# LED_Readout_Resistors.net
KiCad netlist of a schematic drawn in Altium Designer
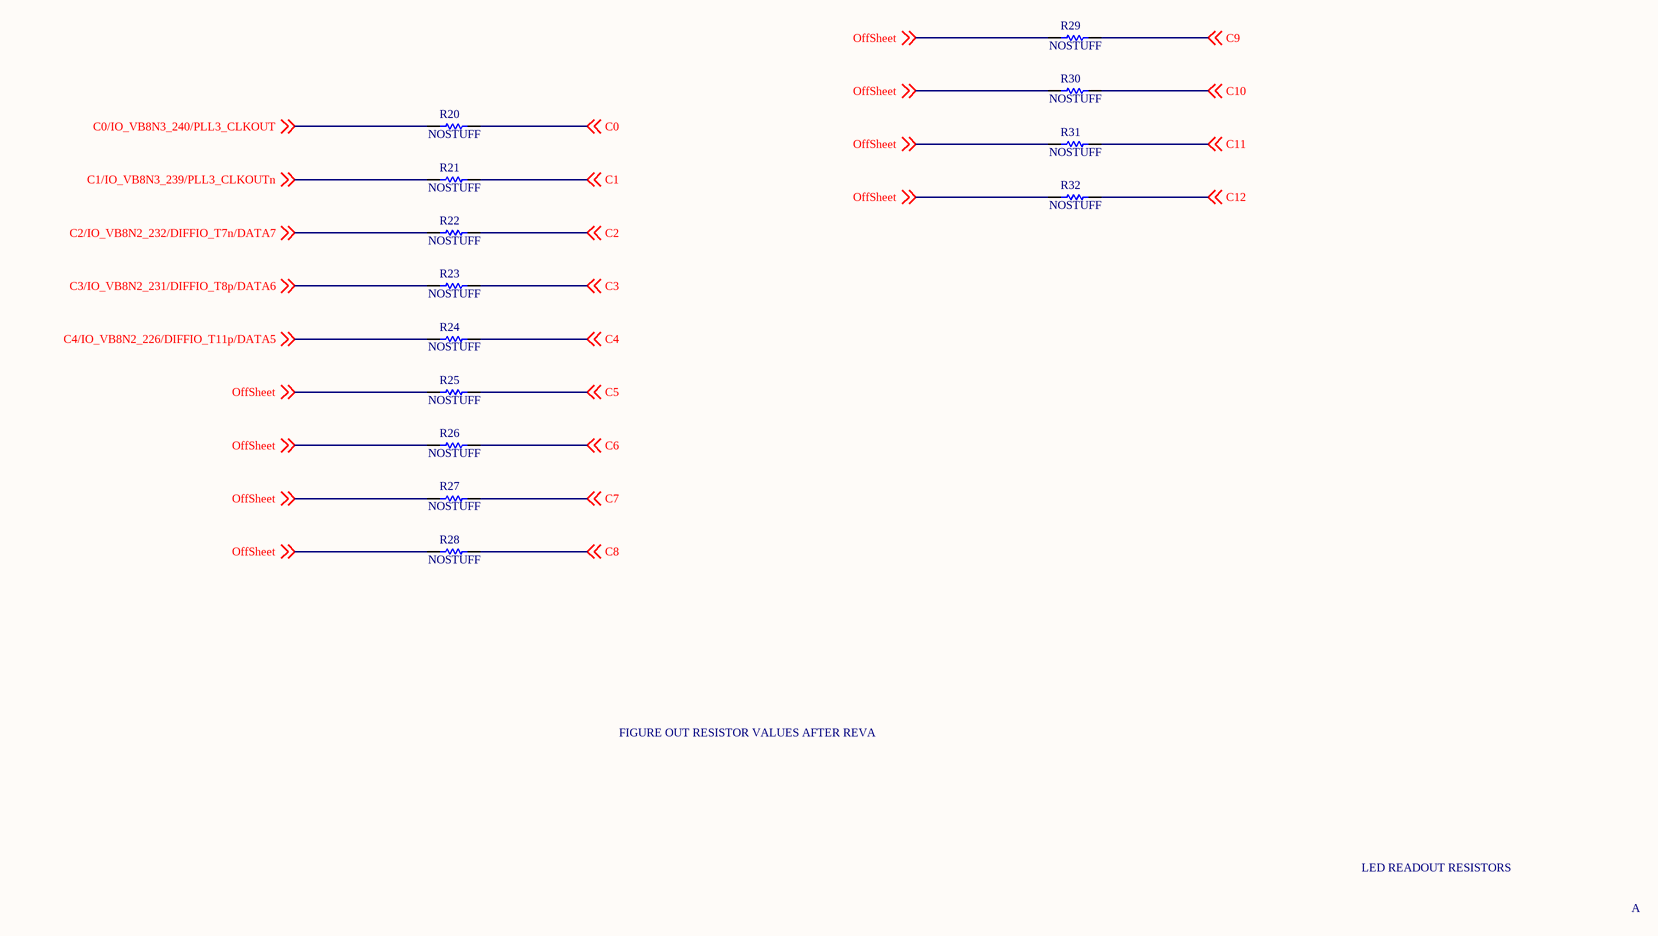
[diagram p0: LED Readout Resistors.SchDoc]

(export (version "E")
  (design (tool "Eeschema 10.0.6"))
  (components
    (comp (ref "R20")
      (value "NOSTUFF")
      (footprint "RES_0603")
      (description "Resistor")
      (fields
        (field (name "Comment") "Figure out ohmage after RevA")
        (field (name "PUBLISHER") "Altium Limited")
      )
      (libsource (lib "Miscellaneous Devices") (part "Res1"))
    )
    (comp (ref "R21")
      (value "NOSTUFF")
      (footprint "RES_0603")
      (description "Resistor")
      (fields
        (field (name "Comment") "Figure out ohmage after RevA")
        (field (name "PUBLISHER") "Altium Limited")
      )
      (libsource (lib "Miscellaneous Devices") (part "Res1"))
    )
    (comp (ref "R22")
      (value "NOSTUFF")
      (footprint "RES_0603")
      (description "Resistor")
      (fields
        (field (name "Comment") "Figure out ohmage after RevA")
        (field (name "PUBLISHER") "Altium Limited")
      )
      (libsource (lib "Miscellaneous Devices") (part "Res1"))
    )
    (comp (ref "R23")
      (value "NOSTUFF")
      (footprint "RES_0603")
      (description "Resistor")
      (fields
        (field (name "Comment") "Figure out ohmage after RevA")
        (field (name "PUBLISHER") "Altium Limited")
      )
      (libsource (lib "Miscellaneous Devices") (part "Res1"))
    )
    (comp (ref "R24")
      (value "NOSTUFF")
      (footprint "RES_0603")
      (description "Resistor")
      (fields
        (field (name "Comment") "Figure out ohmage after RevA")
        (field (name "PUBLISHER") "Altium Limited")
      )
      (libsource (lib "Miscellaneous Devices") (part "Res1"))
    )
    (comp (ref "R25")
      (value "NOSTUFF")
      (footprint "RES_0603")
      (description "Resistor")
      (fields
        (field (name "Comment") "Figure out ohmage after RevA")
        (field (name "PUBLISHER") "Altium Limited")
      )
      (libsource (lib "Miscellaneous Devices") (part "Res1"))
    )
    (comp (ref "R26")
      (value "NOSTUFF")
      (footprint "RES_0603")
      (description "Resistor")
      (fields
        (field (name "Comment") "Figure out ohmage after RevA")
        (field (name "PUBLISHER") "Altium Limited")
      )
      (libsource (lib "Miscellaneous Devices") (part "Res1"))
    )
    (comp (ref "R27")
      (value "NOSTUFF")
      (footprint "RES_0603")
      (description "Resistor")
      (fields
        (field (name "Comment") "Figure out ohmage after RevA")
        (field (name "PUBLISHER") "Altium Limited")
      )
      (libsource (lib "Miscellaneous Devices") (part "Res1"))
    )
    (comp (ref "R28")
      (value "NOSTUFF")
      (footprint "RES_0603")
      (description "Resistor")
      (fields
        (field (name "Comment") "Figure out ohmage after RevA")
        (field (name "PUBLISHER") "Altium Limited")
      )
      (libsource (lib "Miscellaneous Devices") (part "Res1"))
    )
    (comp (ref "R29")
      (value "NOSTUFF")
      (footprint "RES_0603")
      (description "Resistor")
      (fields
        (field (name "Comment") "Figure out ohmage after RevA")
        (field (name "PUBLISHER") "Altium Limited")
      )
      (libsource (lib "Miscellaneous Devices") (part "Res1"))
    )
    (comp (ref "R30")
      (value "NOSTUFF")
      (footprint "RES_0603")
      (description "Resistor")
      (fields
        (field (name "Comment") "Figure out ohmage after RevA")
        (field (name "PUBLISHER") "Altium Limited")
      )
      (libsource (lib "Miscellaneous Devices") (part "Res1"))
    )
    (comp (ref "R31")
      (value "NOSTUFF")
      (footprint "RES_0603")
      (description "Resistor")
      (fields
        (field (name "Comment") "Figure out ohmage after RevA")
        (field (name "PUBLISHER") "Altium Limited")
      )
      (libsource (lib "Miscellaneous Devices") (part "Res1"))
    )
    (comp (ref "R32")
      (value "NOSTUFF")
      (footprint "RES_0603")
      (description "Resistor")
      (fields
        (field (name "Comment") "Figure out ohmage after RevA")
        (field (name "PUBLISHER") "Altium Limited")
      )
      (libsource (lib "Miscellaneous Devices") (part "Res1"))
    )
  )
  (nets
    (net (code "1") (name "C0") (class "Default")
      (node (ref "R20") (pin "2") (pinfunction "2_2") (pintype "passive"))
    )
    (net (code "2") (name "C0{slash}IO_VB8N3_240{slash}PLL3_CLKOUT") (class "Default")
      (node (ref "R20") (pin "1") (pinfunction "1_1") (pintype "passive"))
    )
    (net (code "3") (name "C1") (class "Default")
      (node (ref "R21") (pin "2") (pinfunction "2_2") (pintype "passive"))
    )
    (net (code "4") (name "C1{slash}IO_VB8N3_239{slash}PLL3_CLKOUTn") (class "Default")
      (node (ref "R21") (pin "1") (pinfunction "1_1") (pintype "passive"))
    )
    (net (code "5") (name "C2") (class "Default")
      (node (ref "R22") (pin "2") (pinfunction "2_2") (pintype "passive"))
    )
    (net (code "6") (name "C2{slash}IO_VB8N2_232{slash}DIFFIO_T7n{slash}DATA7") (class "Default")
      (node (ref "R22") (pin "1") (pinfunction "1_1") (pintype "passive"))
    )
    (net (code "7") (name "C3") (class "Default")
      (node (ref "R23") (pin "2") (pinfunction "2_2") (pintype "passive"))
    )
    (net (code "8") (name "C3{slash}IO_VB8N2_231{slash}DIFFIO_T8p{slash}DATA6") (class "Default")
      (node (ref "R23") (pin "1") (pinfunction "1_1") (pintype "passive"))
    )
    (net (code "9") (name "C4") (class "Default")
      (node (ref "R24") (pin "2") (pinfunction "2_2") (pintype "passive"))
    )
    (net (code "10") (name "C4{slash}IO_VB8N2_226{slash}DIFFIO_T11p{slash}DATA5") (class "Default")
      (node (ref "R24") (pin "1") (pinfunction "1_1") (pintype "passive"))
    )
    (net (code "11") (name "C5") (class "Default")
      (node (ref "R25") (pin "2") (pinfunction "2_2") (pintype "passive"))
    )
    (net (code "12") (name "C6") (class "Default")
      (node (ref "R26") (pin "2") (pinfunction "2_2") (pintype "passive"))
    )
    (net (code "13") (name "C7") (class "Default")
      (node (ref "R27") (pin "2") (pinfunction "2_2") (pintype "passive"))
    )
    (net (code "14") (name "C8") (class "Default")
      (node (ref "R28") (pin "2") (pinfunction "2_2") (pintype "passive"))
    )
    (net (code "15") (name "C9") (class "Default")
      (node (ref "R29") (pin "2") (pinfunction "2_2") (pintype "passive"))
    )
    (net (code "16") (name "C10") (class "Default")
      (node (ref "R30") (pin "2") (pinfunction "2_2") (pintype "passive"))
    )
    (net (code "17") (name "C11") (class "Default")
      (node (ref "R31") (pin "2") (pinfunction "2_2") (pintype "passive"))
    )
    (net (code "18") (name "C12") (class "Default")
      (node (ref "R32") (pin "2") (pinfunction "2_2") (pintype "passive"))
    )
    (net (code "19") (name "OffSheet") (class "Default")
      (node (ref "R25") (pin "1") (pinfunction "1_1") (pintype "passive"))
      (node (ref "R26") (pin "1") (pinfunction "1_1") (pintype "passive"))
      (node (ref "R27") (pin "1") (pinfunction "1_1") (pintype "passive"))
      (node (ref "R28") (pin "1") (pinfunction "1_1") (pintype "passive"))
      (node (ref "R29") (pin "1") (pinfunction "1_1") (pintype "passive"))
      (node (ref "R30") (pin "1") (pinfunction "1_1") (pintype "passive"))
      (node (ref "R31") (pin "1") (pinfunction "1_1") (pintype "passive"))
      (node (ref "R32") (pin "1") (pinfunction "1_1") (pintype "passive"))
    )
  )
)
